# lodev-s76s.net
KiCad netlist of a schematic drawn in EAGLE
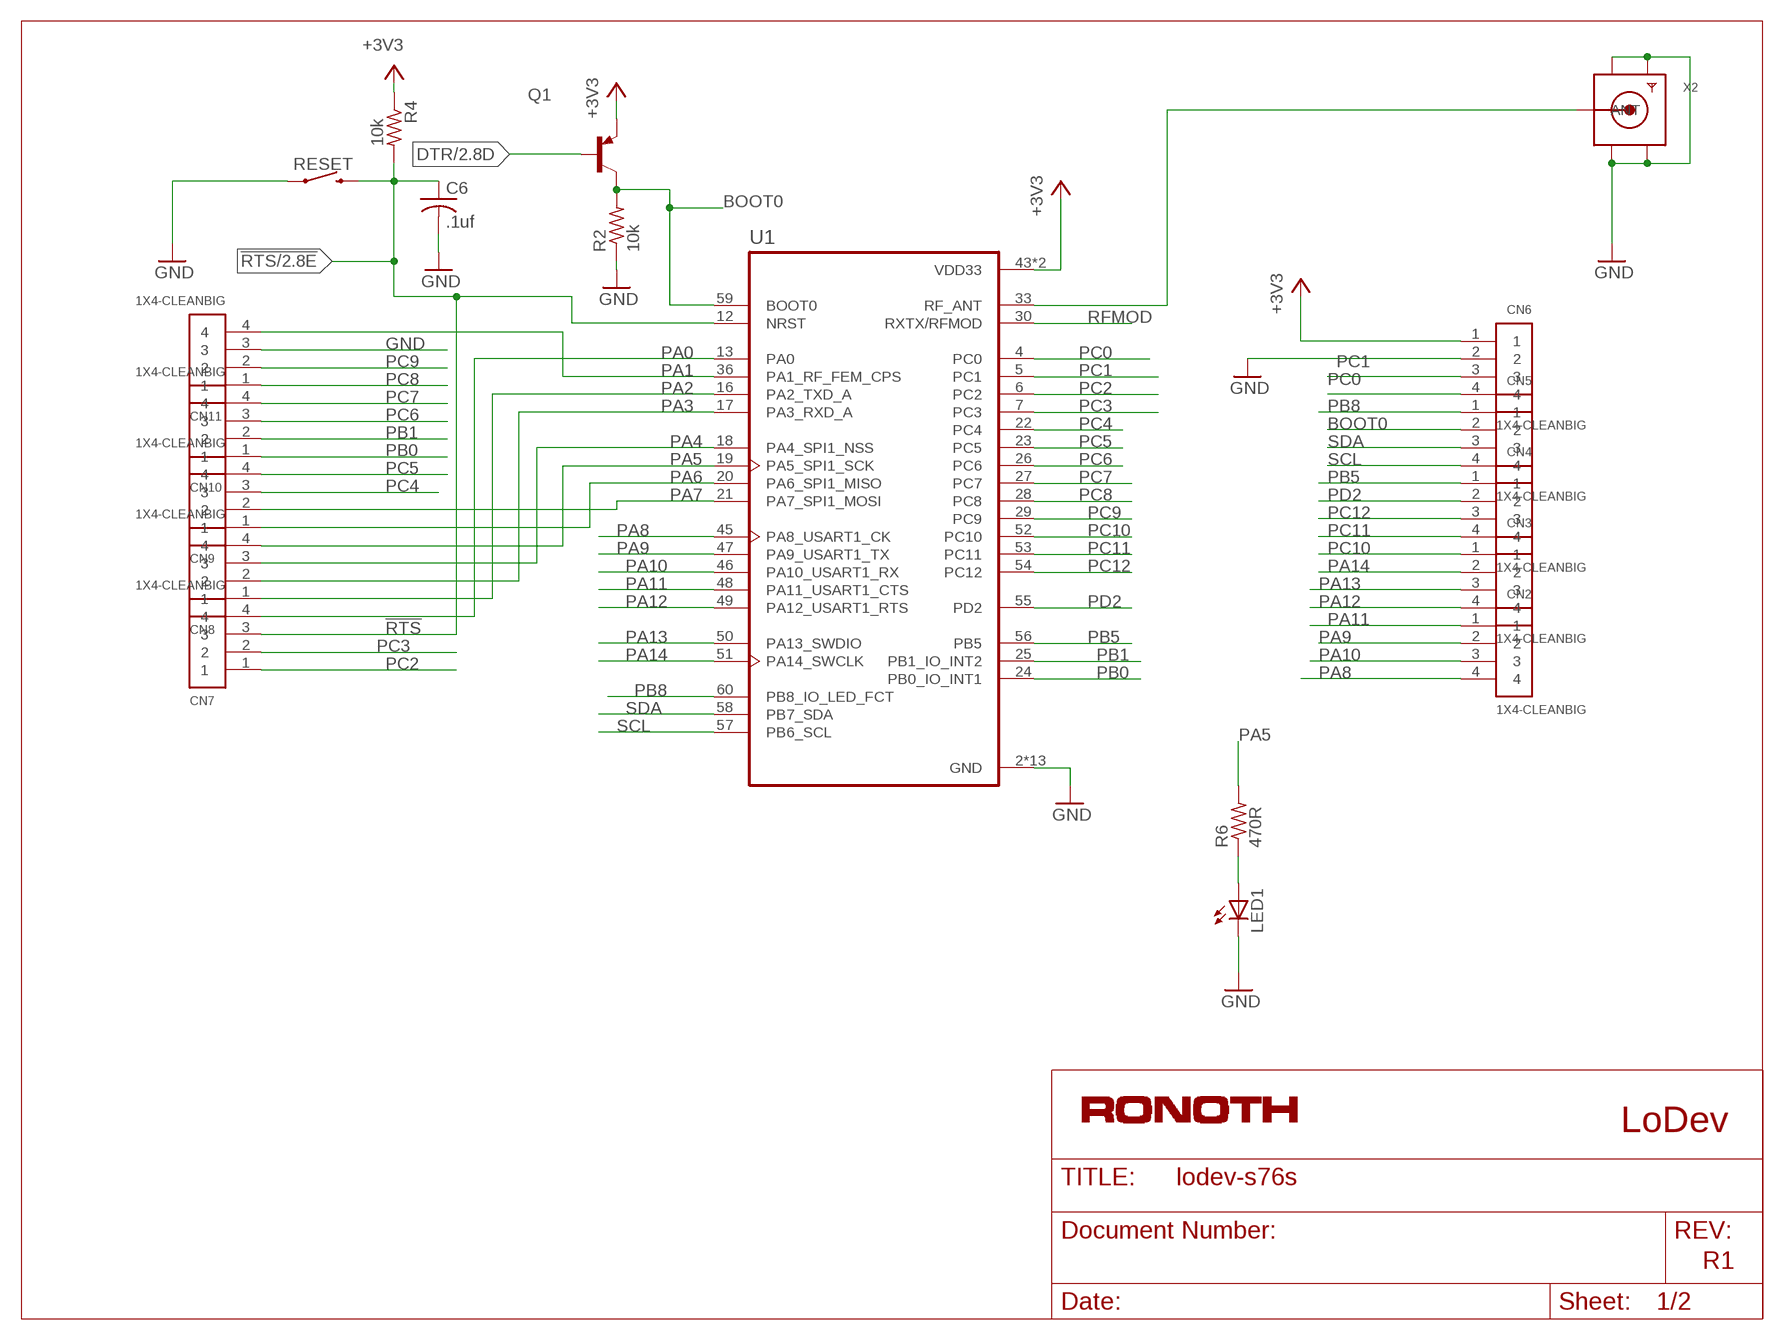
[diagram p0: schematic, sheet 1]
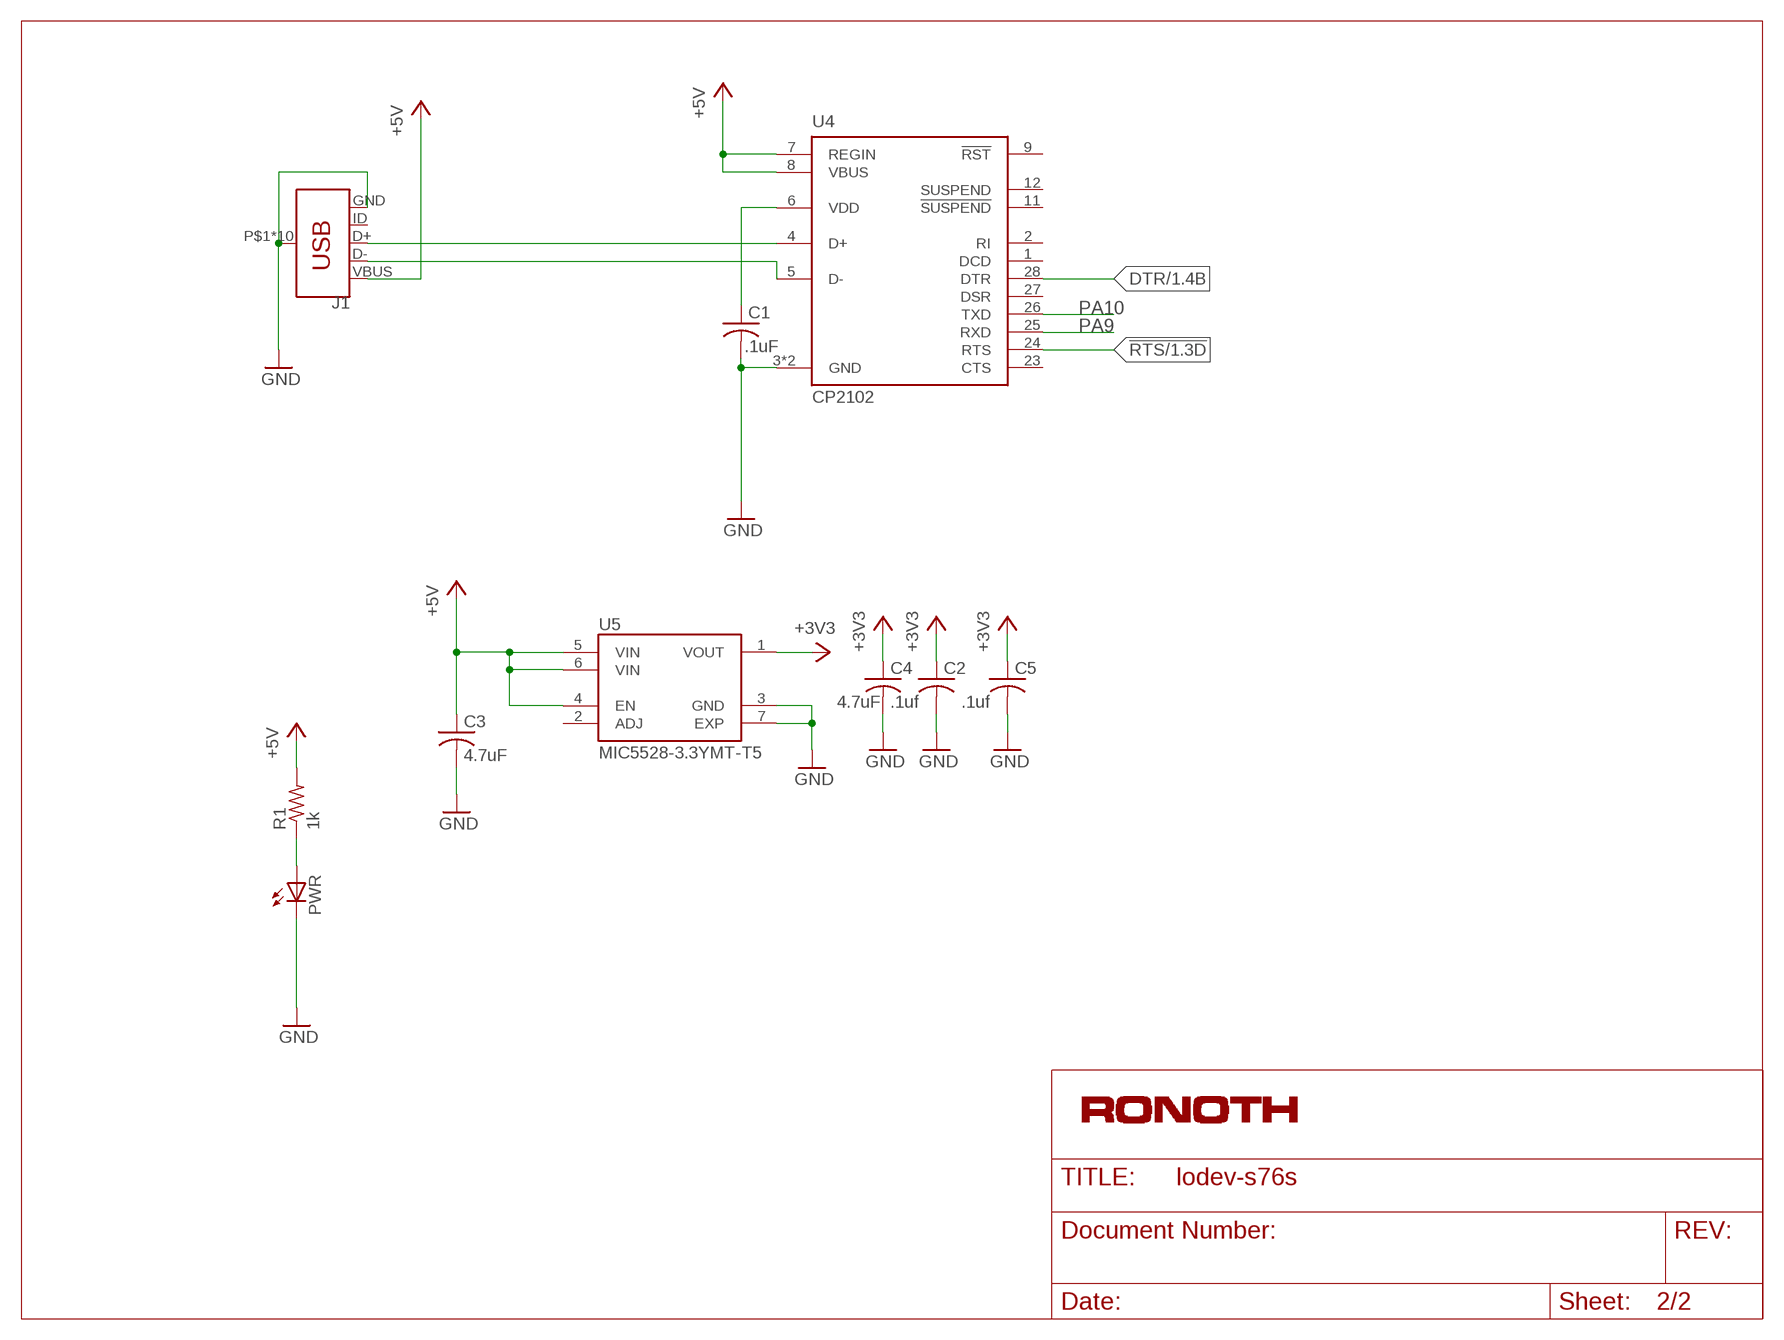
[diagram p1: schematic, sheet 2]

(export (version "E")
  (design (tool "Eeschema 10.0.6"))
  (components
    (comp (ref "C1")
      (value ".1uF")
      (footprint "eagle-import:C0603K")
      (libsource (lib "eagle-import") (part "C-USC0603K"))
    )
    (comp (ref "C2")
      (value ".1uf")
      (footprint "eagle-import:C0603K")
      (libsource (lib "eagle-import") (part "C-USC0603K"))
    )
    (comp (ref "C3")
      (value "4.7uF")
      (footprint "eagle-import:C0603K")
      (libsource (lib "eagle-import") (part "C-USC0603K"))
    )
    (comp (ref "C4")
      (value "4.7uF")
      (footprint "eagle-import:C0603K")
      (libsource (lib "eagle-import") (part "C-USC0603K"))
    )
    (comp (ref "C5")
      (value ".1uf")
      (footprint "eagle-import:C0603K")
      (libsource (lib "eagle-import") (part "C-USC0603K"))
    )
    (comp (ref "J1")
      (value "USB_MICRO-B")
      (footprint "eagle-import:USB-MICROB-PTH")
      (libsource (lib "eagle-import") (part "USB_MICRO-B"))
    )
    (comp (ref "PWR")
      (value "LEDCHIPLED_0603")
      (footprint "eagle-import:CHIPLED_0603")
      (libsource (lib "eagle-import") (part "LEDCHIPLED_0603"))
    )
    (comp (ref "R1")
      (value "1k")
      (footprint "eagle-import:R0603")
      (libsource (lib "eagle-import") (part "R-US_R0603"))
    )
    (comp (ref "U4")
      (value "CP2102")
      (footprint "eagle-import:MLP28")
      (fields (field (name "MF") "FARNELL") (field (name "MPN") "CP2102-GM"))
      (libsource (lib "eagle-import") (part "CP2102"))
    )
    (comp (ref "U5")
      (value "MIC5528-3.3YMT-T5")
      (footprint "eagle-import:SON50P160X160X60-7N")
      (fields (field (name "MF") "Microchip") (field (name "MP") "MIC94325YMT-TR"))
      (libsource (lib "eagle-import") (part "MIC94325YMT-TR"))
    )
    (comp (ref "C6")
      (value ".1uf")
      (footprint "eagle-import:C0603K")
      (libsource (lib "eagle-import") (part "C-USC0603K"))
    )
    (comp (ref "CN2")
      (value "1X4-CLEANBIG")
      (footprint "eagle-import:1X04-CLEANBIG")
      (libsource (lib "eagle-import") (part "1X4-CLEANBIG"))
    )
    (comp (ref "CN3")
      (value "1X4-CLEANBIG")
      (footprint "eagle-import:1X04-CLEANBIG")
      (libsource (lib "eagle-import") (part "1X4-CLEANBIG"))
    )
    (comp (ref "CN4")
      (value "1X4-CLEANBIG")
      (footprint "eagle-import:1X04-CLEANBIG")
      (libsource (lib "eagle-import") (part "1X4-CLEANBIG"))
    )
    (comp (ref "CN5")
      (value "1X4-CLEANBIG")
      (footprint "eagle-import:1X04-CLEANBIG")
      (libsource (lib "eagle-import") (part "1X4-CLEANBIG"))
    )
    (comp (ref "CN6")
      (value "1X4-CLEANBIG")
      (footprint "eagle-import:1X04-CLEANBIG")
      (libsource (lib "eagle-import") (part "1X4-CLEANBIG"))
    )
    (comp (ref "CN7")
      (value "1X4-CLEANBIG")
      (footprint "eagle-import:1X04-CLEANBIG")
      (libsource (lib "eagle-import") (part "1X4-CLEANBIG"))
    )
    (comp (ref "CN8")
      (value "1X4-CLEANBIG")
      (footprint "eagle-import:1X04-CLEANBIG")
      (libsource (lib "eagle-import") (part "1X4-CLEANBIG"))
    )
    (comp (ref "CN9")
      (value "1X4-CLEANBIG")
      (footprint "eagle-import:1X04-CLEANBIG")
      (libsource (lib "eagle-import") (part "1X4-CLEANBIG"))
    )
    (comp (ref "CN10")
      (value "1X4-CLEANBIG")
      (footprint "eagle-import:1X04-CLEANBIG")
      (libsource (lib "eagle-import") (part "1X4-CLEANBIG"))
    )
    (comp (ref "CN11")
      (value "1X4-CLEANBIG")
      (footprint "eagle-import:1X04-CLEANBIG")
      (libsource (lib "eagle-import") (part "1X4-CLEANBIG"))
    )
    (comp (ref "LED1")
      (value "LEDCHIPLED_0603")
      (footprint "eagle-import:CHIPLED_0603")
      (libsource (lib "eagle-import") (part "LEDCHIPLED_0603"))
    )
    (comp (ref "Q1")
      (value "TRANSISTOR_BJT_PNP-SOT-23-BCE")
      (footprint "eagle-import:SOT-23")
      (libsource (lib "eagle-import") (part "TRANSISTOR_BJT_PNP-SOT-23-BCE"))
    )
    (comp (ref "R2")
      (value "10k")
      (footprint "eagle-import:R0603")
      (libsource (lib "eagle-import") (part "R-US_R0603"))
    )
    (comp (ref "R4")
      (value "10k")
      (footprint "eagle-import:R0603")
      (libsource (lib "eagle-import") (part "R-US_R0603"))
    )
    (comp (ref "R6")
      (value "470R")
      (footprint "eagle-import:R0603")
      (libsource (lib "eagle-import") (part "R-US_R0603"))
    )
    (comp (ref "RESET")
      (value "MOMENTARY-SWITCH-SPST-SMD-6.0X3.5MM")
      (footprint "eagle-import:TACTILE_SWITCH_SMD_6.0X3.5MM")
      (libsource (lib "eagle-import") (part "MOMENTARY-SWITCH-SPST-SMD-6.0X3.5MM"))
    )
    (comp (ref "U1")
      (value "S76S")
      (footprint "eagle-import:ACSIP_S76S")
      (fields (field (name "MF") "AcSIP") (field (name "MP") "S76s"))
      (libsource (lib "eagle-import") (part "S76S"))
    )
    (comp (ref "X2")
      (value "SMACONNECTOR_EDGE")
      (footprint "eagle-import:SMA_EDGELAUNCH")
      (libsource (lib "eagle-import") (part "SMACONNECTOR_EDGE"))
    )
  )
  (nets
    (net (code "1") (name "+3V3") (class "Default")
      (node (ref "C2") (pin "1") (pinfunction "1_1") (pintype "passive"))
      (node (ref "C4") (pin "1") (pinfunction "1_1") (pintype "passive"))
      (node (ref "C5") (pin "1") (pinfunction "1_1") (pintype "passive"))
      (node (ref "CN6") (pin "1") (pinfunction "1_1") (pintype "bidirectional"))
      (node (ref "Q1") (pin "3") (pinfunction "E_3") (pintype "passive"))
      (node (ref "R4") (pin "1") (pinfunction "1_1") (pintype "passive"))
      (node (ref "U1") (pin "43") (pinfunction "VDD33_43") (pintype "power_in"))
      (node (ref "U1") (pin "44") (pinfunction "VDD33_44") (pintype "power_in"))
      (node (ref "U5") (pin "1") (pinfunction "VOUT_1") (pintype "output"))
    )
    (net (code "2") (name "+5V") (class "Default")
      (node (ref "C3") (pin "1") (pinfunction "1_1") (pintype "passive"))
      (node (ref "J1") (pin "VBUS") (pinfunction "VBUS_VBUS") (pintype "power_in"))
      (node (ref "R1") (pin "2") (pinfunction "2_2") (pintype "passive"))
      (node (ref "U4") (pin "7") (pinfunction "REGIN_7") (pintype "passive"))
      (node (ref "U4") (pin "8") (pinfunction "VBUS_8") (pintype "input"))
      (node (ref "U5") (pin "4") (pinfunction "EN_4") (pintype "input"))
      (node (ref "U5") (pin "5") (pinfunction "VIN_5") (pintype "input"))
      (node (ref "U5") (pin "6") (pinfunction "VIN_6") (pintype "input"))
    )
    (net (code "3") (name "BOOT0") (class "Default")
      (node (ref "CN5") (pin "2") (pinfunction "2_2") (pintype "bidirectional"))
      (node (ref "Q1") (pin "2") (pinfunction "C_2") (pintype "passive"))
      (node (ref "R2") (pin "2") (pinfunction "2_2") (pintype "passive"))
      (node (ref "U1") (pin "59") (pinfunction "BOOT0_59") (pintype "input"))
    )
    (net (code "4") (name "DTR") (class "Default")
      (node (ref "Q1") (pin "1") (pinfunction "B_1") (pintype "passive"))
      (node (ref "U4") (pin "28") (pinfunction "DTR_28") (pintype "output"))
    )
    (net (code "5") (name "GND") (class "Default")
      (node (ref "C1") (pin "2") (pinfunction "2_2") (pintype "passive"))
      (node (ref "C2") (pin "2") (pinfunction "2_2") (pintype "passive"))
      (node (ref "C3") (pin "2") (pinfunction "2_2") (pintype "passive"))
      (node (ref "C4") (pin "2") (pinfunction "2_2") (pintype "passive"))
      (node (ref "C5") (pin "2") (pinfunction "2_2") (pintype "passive"))
      (node (ref "C6") (pin "2") (pinfunction "2_2") (pintype "passive"))
      (node (ref "CN11") (pin "3") (pinfunction "3_3") (pintype "bidirectional"))
      (node (ref "CN6") (pin "2") (pinfunction "2_2") (pintype "bidirectional"))
      (node (ref "J1") (pin "GND") (pinfunction "GND_GND") (pintype "power_in"))
      (node (ref "J1") (pin "P$1") (pinfunction "SHIELD_P$1") (pintype "bidirectional"))
      (node (ref "J1") (pin "P$10") (pinfunction "SHIELD_P$10") (pintype "bidirectional"))
      (node (ref "J1") (pin "P$12") (pinfunction "SHIELD_P$12") (pintype "bidirectional"))
      (node (ref "J1") (pin "P$3") (pinfunction "SHIELD_P$3") (pintype "bidirectional"))
      (node (ref "J1") (pin "P$4") (pinfunction "SHIELD_P$4") (pintype "bidirectional"))
      (node (ref "J1") (pin "P$8") (pinfunction "SHIELD_P$8") (pintype "bidirectional"))
      (node (ref "J1") (pin "SHEILD2") (pinfunction "SHIELD_SHEILD2") (pintype "bidirectional"))
      (node (ref "J1") (pin "SHIELD") (pinfunction "SHIELD_SHIELD") (pintype "bidirectional"))
      (node (ref "J1") (pin "SHIELD3") (pinfunction "SHIELD_SHIELD3") (pintype "bidirectional"))
      (node (ref "J1") (pin "SHIELD4") (pinfunction "SHIELD_SHIELD4") (pintype "bidirectional"))
      (node (ref "LED1") (pin "C") (pinfunction "C_C") (pintype "passive"))
      (node (ref "PWR") (pin "C") (pinfunction "C_C") (pintype "passive"))
      (node (ref "R2") (pin "1") (pinfunction "1_1") (pintype "passive"))
      (node (ref "RESET") (pin "1") (pinfunction "1_1") (pintype "passive"))
      (node (ref "U1") (pin "14") (pinfunction "GND_14") (pintype "power_in"))
      (node (ref "U1") (pin "15") (pinfunction "GND_15") (pintype "power_in"))
      (node (ref "U1") (pin "2") (pinfunction "GND_2") (pintype "power_in"))
      (node (ref "U1") (pin "3") (pinfunction "GND_3") (pintype "power_in"))
      (node (ref "U1") (pin "31") (pinfunction "GND_31") (pintype "power_in"))
      (node (ref "U1") (pin "32") (pinfunction "GND_32") (pintype "power_in"))
      (node (ref "U1") (pin "34") (pinfunction "GND_34") (pintype "power_in"))
      (node (ref "U1") (pin "35") (pinfunction "GND_35") (pintype "power_in"))
      (node (ref "U1") (pin "37") (pinfunction "GND_37") (pintype "power_in"))
      (node (ref "U1") (pin "39") (pinfunction "GND_39") (pintype "power_in"))
      (node (ref "U1") (pin "41") (pinfunction "GND_41") (pintype "power_in"))
      (node (ref "U1") (pin "61") (pinfunction "GND_61") (pintype "power_in"))
      (node (ref "U1") (pin "62") (pinfunction "GND_62") (pintype "power_in"))
      (node (ref "U4") (pin "3") (pinfunction "GND_3") (pintype "power_in"))
      (node (ref "U4") (pin "EXP") (pinfunction "GND_EXP") (pintype "power_in"))
      (node (ref "U5") (pin "3") (pinfunction "GND_3") (pintype "power_in"))
      (node (ref "U5") (pin "7") (pinfunction "EXP_7") (pintype "power_in"))
      (node (ref "X2") (pin "GND@1") (pinfunction "GND4_GND@1") (pintype "power_in"))
      (node (ref "X2") (pin "GND@2") (pinfunction "GND3_GND@2") (pintype "power_in"))
      (node (ref "X2") (pin "GND@3") (pinfunction "GND2_GND@3") (pintype "power_in"))
      (node (ref "X2") (pin "GND@4") (pinfunction "GND1_GND@4") (pintype "power_in"))
    )
    (net (code "6") (name "Net-(LED1-PadA)") (class "Default")
      (node (ref "LED1") (pin "A") (pinfunction "A_A") (pintype "passive"))
      (node (ref "R6") (pin "1") (pinfunction "1_1") (pintype "passive"))
    )
    (net (code "7") (name "Net-(PWR-PadA)") (class "Default")
      (node (ref "PWR") (pin "A") (pinfunction "A_A") (pintype "passive"))
      (node (ref "R1") (pin "1") (pinfunction "1_1") (pintype "passive"))
    )
    (net (code "8") (name "Net-(U1-RF_ANT)") (class "Default")
      (node (ref "U1") (pin "33") (pinfunction "RF_ANT_33") (pintype "bidirectional"))
      (node (ref "X2") (pin "P") (pinfunction "ANT_P") (pintype "bidirectional"))
    )
    (net (code "9") (name "Net-(U4-D+)") (class "Default")
      (node (ref "J1") (pin "D+") (pinfunction "D+_D+") (pintype "bidirectional"))
      (node (ref "U4") (pin "4") (pinfunction "D+_4") (pintype "bidirectional"))
    )
    (net (code "10") (name "Net-(U4-D-)") (class "Default")
      (node (ref "J1") (pin "D-") (pinfunction "D-_D-") (pintype "bidirectional"))
      (node (ref "U4") (pin "5") (pinfunction "D-_5") (pintype "bidirectional"))
    )
    (net (code "11") (name "Net-(U4-VDD)") (class "Default")
      (node (ref "C1") (pin "1") (pinfunction "1_1") (pintype "passive"))
      (node (ref "U4") (pin "6") (pinfunction "VDD_6") (pintype "power_in"))
    )
    (net (code "12") (name "PA0") (class "Default")
      (node (ref "CN7") (pin "4") (pinfunction "4_4") (pintype "bidirectional"))
      (node (ref "U1") (pin "13") (pinfunction "PA0_13") (pintype "bidirectional"))
    )
    (net (code "13") (name "PA1") (class "Default")
      (node (ref "CN11") (pin "4") (pinfunction "4_4") (pintype "bidirectional"))
      (node (ref "U1") (pin "36") (pinfunction "PA1_RF_FEM_CPS_36") (pintype "bidirectional"))
    )
    (net (code "14") (name "PA2") (class "Default")
      (node (ref "CN8") (pin "1") (pinfunction "1_1") (pintype "bidirectional"))
      (node (ref "U1") (pin "16") (pinfunction "PA2_TXD_A_16") (pintype "bidirectional"))
    )
    (net (code "15") (name "PA3") (class "Default")
      (node (ref "CN8") (pin "2") (pinfunction "2_2") (pintype "bidirectional"))
      (node (ref "U1") (pin "17") (pinfunction "PA3_RXD_A_17") (pintype "bidirectional"))
    )
    (net (code "16") (name "PA4") (class "Default")
      (node (ref "CN8") (pin "3") (pinfunction "3_3") (pintype "bidirectional"))
      (node (ref "U1") (pin "18") (pinfunction "PA4_SPI1_NSS_18") (pintype "bidirectional"))
    )
    (net (code "17") (name "PA5") (class "Default")
      (node (ref "CN8") (pin "4") (pinfunction "4_4") (pintype "bidirectional"))
      (node (ref "R6") (pin "2") (pinfunction "2_2") (pintype "passive"))
      (node (ref "U1") (pin "19") (pinfunction "PA5_SPI1_SCK_19") (pintype "bidirectional"))
    )
    (net (code "18") (name "PA6") (class "Default")
      (node (ref "CN9") (pin "1") (pinfunction "1_1") (pintype "bidirectional"))
      (node (ref "U1") (pin "20") (pinfunction "PA6_SPI1_MISO_20") (pintype "bidirectional"))
    )
    (net (code "19") (name "PA7") (class "Default")
      (node (ref "CN9") (pin "2") (pinfunction "2_2") (pintype "bidirectional"))
      (node (ref "U1") (pin "21") (pinfunction "PA7_SPI1_MOSI_21") (pintype "bidirectional"))
    )
    (net (code "20") (name "PA8") (class "Default")
      (node (ref "CN2") (pin "4") (pinfunction "4_4") (pintype "bidirectional"))
      (node (ref "U1") (pin "45") (pinfunction "PA8_USART1_CK_45") (pintype "bidirectional"))
    )
    (net (code "21") (name "PA9") (class "Default")
      (node (ref "CN2") (pin "2") (pinfunction "2_2") (pintype "bidirectional"))
      (node (ref "U1") (pin "47") (pinfunction "PA9_USART1_TX_47") (pintype "bidirectional"))
      (node (ref "U4") (pin "25") (pinfunction "RXD_25") (pintype "input"))
    )
    (net (code "22") (name "PA10") (class "Default")
      (node (ref "CN2") (pin "3") (pinfunction "3_3") (pintype "bidirectional"))
      (node (ref "U1") (pin "46") (pinfunction "PA10_USART1_RX_46") (pintype "bidirectional"))
      (node (ref "U4") (pin "26") (pinfunction "TXD_26") (pintype "output"))
    )
    (net (code "23") (name "PA11") (class "Default")
      (node (ref "CN2") (pin "1") (pinfunction "1_1") (pintype "bidirectional"))
      (node (ref "U1") (pin "48") (pinfunction "PA11_USART1_CTS_48") (pintype "bidirectional"))
    )
    (net (code "24") (name "PA12") (class "Default")
      (node (ref "CN3") (pin "4") (pinfunction "4_4") (pintype "bidirectional"))
      (node (ref "U1") (pin "49") (pinfunction "PA12_USART1_RTS_49") (pintype "bidirectional"))
    )
    (net (code "25") (name "PA13") (class "Default")
      (node (ref "CN3") (pin "3") (pinfunction "3_3") (pintype "bidirectional"))
      (node (ref "U1") (pin "50") (pinfunction "PA13_SWDIO_50") (pintype "bidirectional"))
    )
    (net (code "26") (name "PA14") (class "Default")
      (node (ref "CN3") (pin "2") (pinfunction "2_2") (pintype "bidirectional"))
      (node (ref "U1") (pin "51") (pinfunction "PA14_SWCLK_51") (pintype "bidirectional"))
    )
    (net (code "27") (name "PB0") (class "Default")
      (node (ref "CN10") (pin "1") (pinfunction "1_1") (pintype "bidirectional"))
      (node (ref "U1") (pin "24") (pinfunction "PB0_IO_INT1_24") (pintype "bidirectional"))
    )
    (net (code "28") (name "PB1") (class "Default")
      (node (ref "CN10") (pin "2") (pinfunction "2_2") (pintype "bidirectional"))
      (node (ref "U1") (pin "25") (pinfunction "PB1_IO_INT2_25") (pintype "bidirectional"))
    )
    (net (code "29") (name "PB5") (class "Default")
      (node (ref "CN4") (pin "1") (pinfunction "1_1") (pintype "bidirectional"))
      (node (ref "U1") (pin "56") (pinfunction "PB5_56") (pintype "bidirectional"))
    )
    (net (code "30") (name "PB8") (class "Default")
      (node (ref "CN5") (pin "1") (pinfunction "1_1") (pintype "bidirectional"))
      (node (ref "U1") (pin "60") (pinfunction "PB8_IO_LED_FCT_60") (pintype "bidirectional"))
    )
    (net (code "31") (name "PC0") (class "Default")
      (node (ref "CN6") (pin "4") (pinfunction "4_4") (pintype "bidirectional"))
      (node (ref "U1") (pin "4") (pinfunction "PC0_4") (pintype "bidirectional"))
    )
    (net (code "32") (name "PC1") (class "Default")
      (node (ref "CN6") (pin "3") (pinfunction "3_3") (pintype "bidirectional"))
      (node (ref "U1") (pin "5") (pinfunction "PC1_5") (pintype "bidirectional"))
    )
    (net (code "33") (name "PC2") (class "Default")
      (node (ref "CN7") (pin "1") (pinfunction "1_1") (pintype "bidirectional"))
      (node (ref "U1") (pin "6") (pinfunction "PC2_6") (pintype "bidirectional"))
    )
    (net (code "34") (name "PC3") (class "Default")
      (node (ref "CN7") (pin "2") (pinfunction "2_2") (pintype "bidirectional"))
      (node (ref "U1") (pin "7") (pinfunction "PC3_7") (pintype "bidirectional"))
    )
    (net (code "35") (name "PC4") (class "Default")
      (node (ref "CN9") (pin "3") (pinfunction "3_3") (pintype "bidirectional"))
      (node (ref "U1") (pin "22") (pinfunction "PC4_22") (pintype "bidirectional"))
    )
    (net (code "36") (name "PC5") (class "Default")
      (node (ref "CN9") (pin "4") (pinfunction "4_4") (pintype "bidirectional"))
      (node (ref "U1") (pin "23") (pinfunction "PC5_23") (pintype "bidirectional"))
    )
    (net (code "37") (name "PC6") (class "Default")
      (node (ref "CN10") (pin "3") (pinfunction "3_3") (pintype "bidirectional"))
      (node (ref "U1") (pin "26") (pinfunction "PC6_26") (pintype "bidirectional"))
    )
    (net (code "38") (name "PC7") (class "Default")
      (node (ref "CN10") (pin "4") (pinfunction "4_4") (pintype "bidirectional"))
      (node (ref "U1") (pin "27") (pinfunction "PC7_27") (pintype "bidirectional"))
    )
    (net (code "39") (name "PC8") (class "Default")
      (node (ref "CN11") (pin "1") (pinfunction "1_1") (pintype "bidirectional"))
      (node (ref "U1") (pin "28") (pinfunction "PC8_28") (pintype "bidirectional"))
    )
    (net (code "40") (name "PC9") (class "Default")
      (node (ref "CN11") (pin "2") (pinfunction "2_2") (pintype "bidirectional"))
      (node (ref "U1") (pin "29") (pinfunction "PC9_29") (pintype "bidirectional"))
    )
    (net (code "41") (name "PC10") (class "Default")
      (node (ref "CN3") (pin "1") (pinfunction "1_1") (pintype "bidirectional"))
      (node (ref "U1") (pin "52") (pinfunction "PC10_52") (pintype "bidirectional"))
    )
    (net (code "42") (name "PC11") (class "Default")
      (node (ref "CN4") (pin "4") (pinfunction "4_4") (pintype "bidirectional"))
      (node (ref "U1") (pin "53") (pinfunction "PC11_53") (pintype "bidirectional"))
    )
    (net (code "43") (name "PC12") (class "Default")
      (node (ref "CN4") (pin "3") (pinfunction "3_3") (pintype "bidirectional"))
      (node (ref "U1") (pin "54") (pinfunction "PC12_54") (pintype "bidirectional"))
    )
    (net (code "44") (name "PD2") (class "Default")
      (node (ref "CN4") (pin "2") (pinfunction "2_2") (pintype "bidirectional"))
      (node (ref "U1") (pin "55") (pinfunction "PD2_55") (pintype "bidirectional"))
    )
    (net (code "45") (name "RFMOD") (class "Default")
      (node (ref "U1") (pin "30") (pinfunction "RXTX/RFMOD_30") (pintype "output"))
    )
    (net (code "46") (name "SCL") (class "Default")
      (node (ref "CN5") (pin "4") (pinfunction "4_4") (pintype "bidirectional"))
      (node (ref "U1") (pin "57") (pinfunction "PB6_SCL_57") (pintype "bidirectional"))
    )
    (net (code "47") (name "SDA") (class "Default")
      (node (ref "CN5") (pin "3") (pinfunction "3_3") (pintype "bidirectional"))
      (node (ref "U1") (pin "58") (pinfunction "PB7_SDA_58") (pintype "bidirectional"))
    )
    (net (code "48") (name "unconnected-(J1-PadID)") (class "Default")
      (node (ref "J1") (pin "ID") (pinfunction "ID_ID") (pintype "bidirectional"))
    )
    (net (code "49") (name "unconnected-(U4-CTS-Pad23)") (class "Default")
      (node (ref "U4") (pin "23") (pinfunction "CTS_23") (pintype "input"))
    )
    (net (code "50") (name "unconnected-(U4-DCD-Pad1)") (class "Default")
      (node (ref "U4") (pin "1") (pinfunction "DCD_1") (pintype "input"))
    )
    (net (code "51") (name "unconnected-(U4-DSR-Pad27)") (class "Default")
      (node (ref "U4") (pin "27") (pinfunction "DSR_27") (pintype "input"))
    )
    (net (code "52") (name "unconnected-(U4-RI-Pad2)") (class "Default")
      (node (ref "U4") (pin "2") (pinfunction "RI_2") (pintype "input"))
    )
    (net (code "53") (name "unconnected-(U4-SUSPEND-Pad12)") (class "Default")
      (node (ref "U4") (pin "12") (pinfunction "SUSPEND_12") (pintype "output"))
    )
    (net (code "54") (name "unconnected-(U4-~{RST}-Pad9)") (class "Default")
      (node (ref "U4") (pin "9") (pinfunction "~{RST}_9") (pintype "bidirectional"))
    )
    (net (code "55") (name "unconnected-(U4-~{SUSPEND}-Pad11)") (class "Default")
      (node (ref "U4") (pin "11") (pinfunction "~{SUSPEND}_11") (pintype "output"))
    )
    (net (code "56") (name "unconnected-(U5-ADJ-Pad2)") (class "Default")
      (node (ref "U5") (pin "2") (pinfunction "ADJ_2") (pintype "passive"))
    )
    (net (code "57") (name "~{RTS}") (class "Default")
      (node (ref "C6") (pin "1") (pinfunction "1_1") (pintype "passive"))
      (node (ref "CN7") (pin "3") (pinfunction "3_3") (pintype "bidirectional"))
      (node (ref "R4") (pin "2") (pinfunction "2_2") (pintype "passive"))
      (node (ref "RESET") (pin "2") (pinfunction "2_2") (pintype "passive"))
      (node (ref "U1") (pin "12") (pinfunction "NRST_12") (pintype "bidirectional"))
      (node (ref "U4") (pin "24") (pinfunction "RTS_24") (pintype "output"))
    )
  )
)
